# Pi_Cellular.net
KiCad netlist of a schematic drawn in Altium Designer
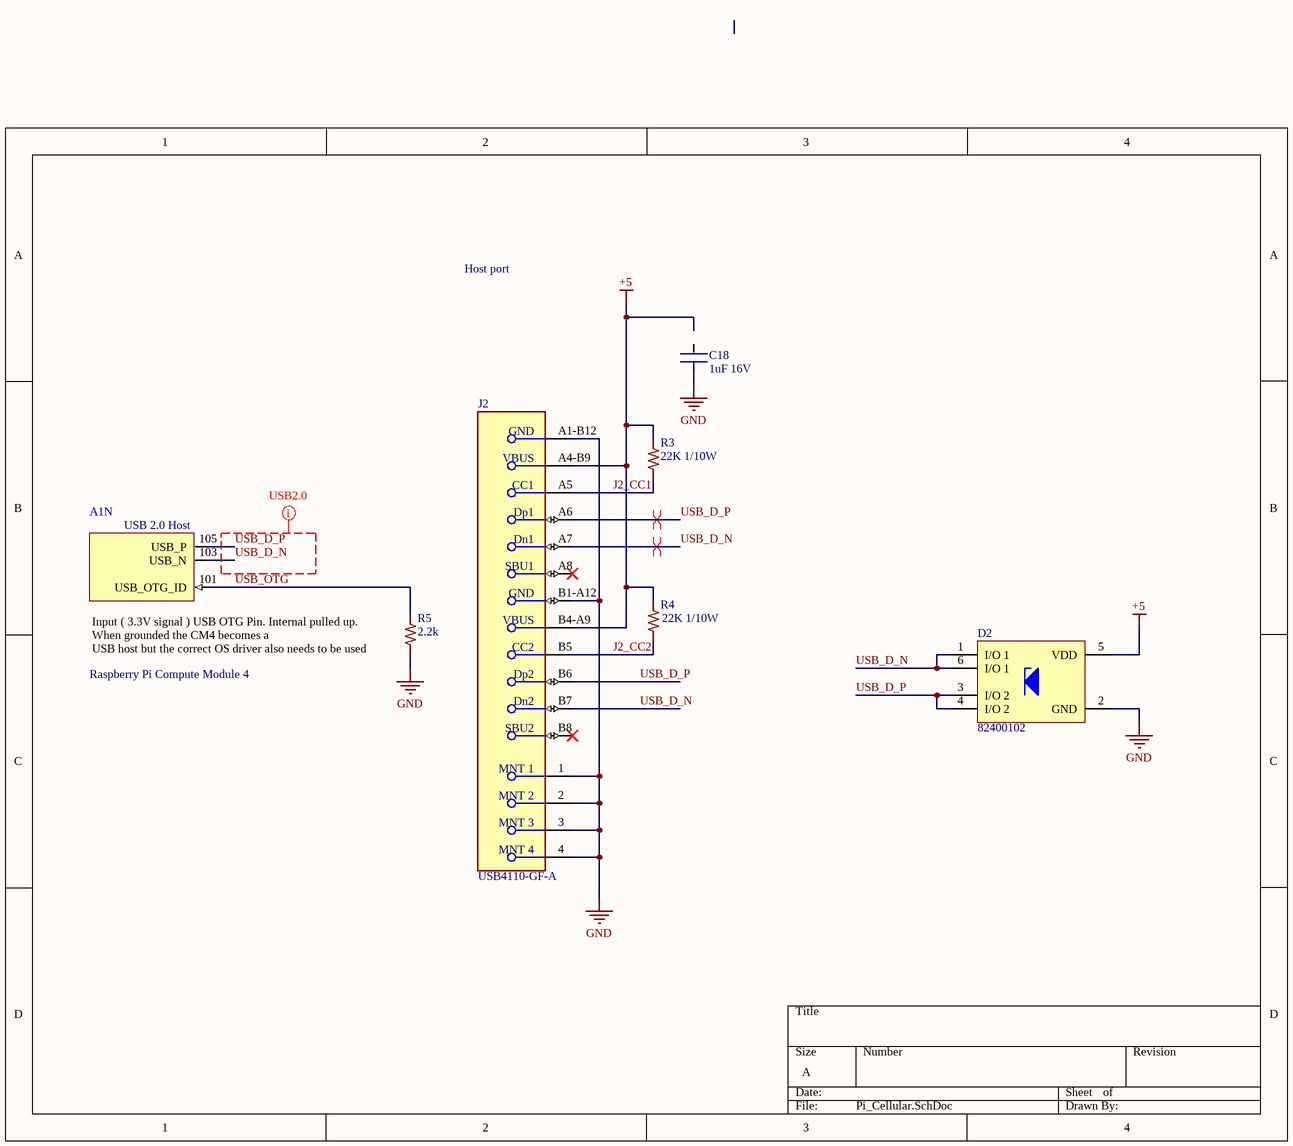
[diagram p0: Pi_Cellular.SchDoc]

(export (version "E")
  (design (tool "Eeschema 10.0.6"))
  (components
    (comp (ref "A1")
      (value "Raspberry Pi Compute Module 4")
      (footprint "CM4-F40C-100DS-0.4v_1.5mm_0mm")
      (description "Raspberry Pi Compute Module 4 by Amornthep Phunsin")
      (libsource (lib "CM4") (part "CM4"))
    )
    (comp (ref "C18")
      (value "1uF 16V")
      (footprint "CAPACITOR_0603")
      (description "CAP CER 1UF 16V X5R 0603")
      (fields (field (name "MPN") "CL10A105KO8NNNC") (field (name "MFR") "Samsung Electro-Mechanics"))
      (libsource (lib "CM4") (part "CL10A105KO8NNNC"))
    )
    (comp (ref "D2")
      (value "82400102")
      (footprint "WE-TVS_SOT23-6L")
      (description "TVS DIODE 5VWM 7.7VC SOT23-6L")
      (fields (field (name "MFR") "Würth Elektronik"))
      (libsource (lib "Altium Content Vault") (part "Diode_2+1 Channel_Unidirectional - 82400102"))
    )
    (comp (ref "J2")
      (value "USB4110-GF-A")
      (footprint "FP-USB4110-GF-A-MFG")
      (description "CONN USB 2.0 TYPE-C R/A SMT")
      (fields
        (field (name "OCTOPART") "https://octopart.com/usb4110-gf-a-gct-103941985")
        (field (name "MANUFACTURER") "GCT")
      )
      (libsource (lib "CM4") (part "USB4110-GF-A"))
    )
    (comp (ref "R3")
      (value "22K 1/10W")
      (footprint "0603R")
      (description "RES SMD 22K OHM 0.1% 1/10W 0603")
      (fields (field (name "MPN") "ERA-3AEB223V") (field (name "MFR") "Panasonic Electronic Components"))
      (libsource (lib "CM4") (part "RESISTOR_0603"))
    )
    (comp (ref "R4")
      (value "22K 1/10W")
      (footprint "0603R")
      (description "RES SMD 22K OHM 0.1% 1/10W 0603")
      (fields
        (field (name "MANUFACTURER") "Panasonic Electronic Components")
        (field (name "MPN") "ERA-3AEB223V")
      )
      (libsource (lib "CM4") (part "RESISTOR_0603"))
    )
    (comp (ref "R5")
      (value "Resistor 0603")
      (footprint "0603R")
      (fields
        (field (name "MANUFACTURER") "YAGEO")
        (field (name "MPN") "RT0603BRD072K2L")
        (field (name "RESISTANCE") "2.2k")
      )
      (libsource (lib "CM4") (part "RESISTOR_0603"))
    )
  )
  (nets
    (net (code "1") (name "+5") (class "Default")
      (node (ref "D2") (pin "5") (pinfunction "VDD_5") (pintype "passive"))
      (node (ref "J2") (pin "A4-B9") (pinfunction "VBUS_A4-B9") (pintype "power_in"))
      (node (ref "J2") (pin "B4-A9") (pinfunction "VBUS_B4-A9") (pintype "power_in"))
      (node (ref "R3") (pin "2") (pinfunction "2_2") (pintype "passive"))
      (node (ref "R4") (pin "2") (pinfunction "2_2") (pintype "passive"))
    )
    (net (code "2") (name "/J2_CC1") (class "Default")
      (node (ref "J2") (pin "A5") (pinfunction "CC1_A5") (pintype "power_in"))
      (node (ref "R3") (pin "1") (pinfunction "1_1") (pintype "passive"))
    )
    (net (code "3") (name "/J2_CC2") (class "Default")
      (node (ref "J2") (pin "B5") (pinfunction "CC2_B5") (pintype "power_in"))
      (node (ref "R4") (pin "1") (pinfunction "1_1") (pintype "passive"))
    )
    (net (code "4") (name "/USB_D_N") (class "Default")
      (node (ref "A1") (pin "103") (pinfunction "USB_N_103") (pintype "passive"))
      (node (ref "D2") (pin "1") (pinfunction "I/O_1_1") (pintype "passive"))
      (node (ref "D2") (pin "6") (pinfunction "I/O_1_6") (pintype "passive"))
      (node (ref "J2") (pin "A7") (pinfunction "Dn1_A7") (pintype "bidirectional"))
      (node (ref "J2") (pin "B7") (pinfunction "Dn2_B7") (pintype "bidirectional"))
    )
    (net (code "5") (name "/USB_D_P") (class "Default")
      (node (ref "A1") (pin "105") (pinfunction "USB_P_105") (pintype "passive"))
      (node (ref "D2") (pin "3") (pinfunction "I/O_2_3") (pintype "passive"))
      (node (ref "D2") (pin "4") (pinfunction "I/O_2_4") (pintype "passive"))
      (node (ref "J2") (pin "A6") (pinfunction "Dp1_A6") (pintype "bidirectional"))
      (node (ref "J2") (pin "B6") (pinfunction "Dp2_B6") (pintype "bidirectional"))
    )
    (net (code "6") (name "/USB_OTG") (class "Default")
      (node (ref "A1") (pin "101") (pinfunction "USB_OTG_ID_101") (pintype "input"))
      (node (ref "R5") (pin "2") (pinfunction "2_2") (pintype "passive"))
    )
    (net (code "7") (name "GND") (class "Default")
      (node (ref "C18") (pin "1") (pinfunction "1_1") (pintype "passive"))
      (node (ref "D2") (pin "2") (pinfunction "GND_2") (pintype "passive"))
      (node (ref "J2") (pin "1") (pinfunction "MNT_1_1") (pintype "passive"))
      (node (ref "J2") (pin "2") (pinfunction "MNT_2_2") (pintype "passive"))
      (node (ref "J2") (pin "3") (pinfunction "MNT_3_3") (pintype "passive"))
      (node (ref "J2") (pin "4") (pinfunction "MNT_4_4") (pintype "passive"))
      (node (ref "J2") (pin "A1-B12") (pinfunction "GND_A1-B12") (pintype "passive"))
      (node (ref "J2") (pin "B1-A12") (pinfunction "GND_B1-A12") (pintype "bidirectional"))
      (node (ref "R5") (pin "1") (pinfunction "1_1") (pintype "passive"))
    )
    (net (code "8") (name "unconnected-(C18-Pad2)") (class "Default")
      (node (ref "C18") (pin "2") (pinfunction "2_2") (pintype "passive"))
    )
    (net (code "9") (name "unconnected-(J2-SBU1-PadA8)") (class "Default")
      (node (ref "J2") (pin "A8") (pinfunction "SBU1_A8") (pintype "bidirectional+no_connect"))
    )
    (net (code "10") (name "unconnected-(J2-SBU2-PadB8)") (class "Default")
      (node (ref "J2") (pin "B8") (pinfunction "SBU2_B8") (pintype "bidirectional+no_connect"))
    )
  )
)
